# pc-001.net
KiCad netlist of a schematic drawn in EAGLE
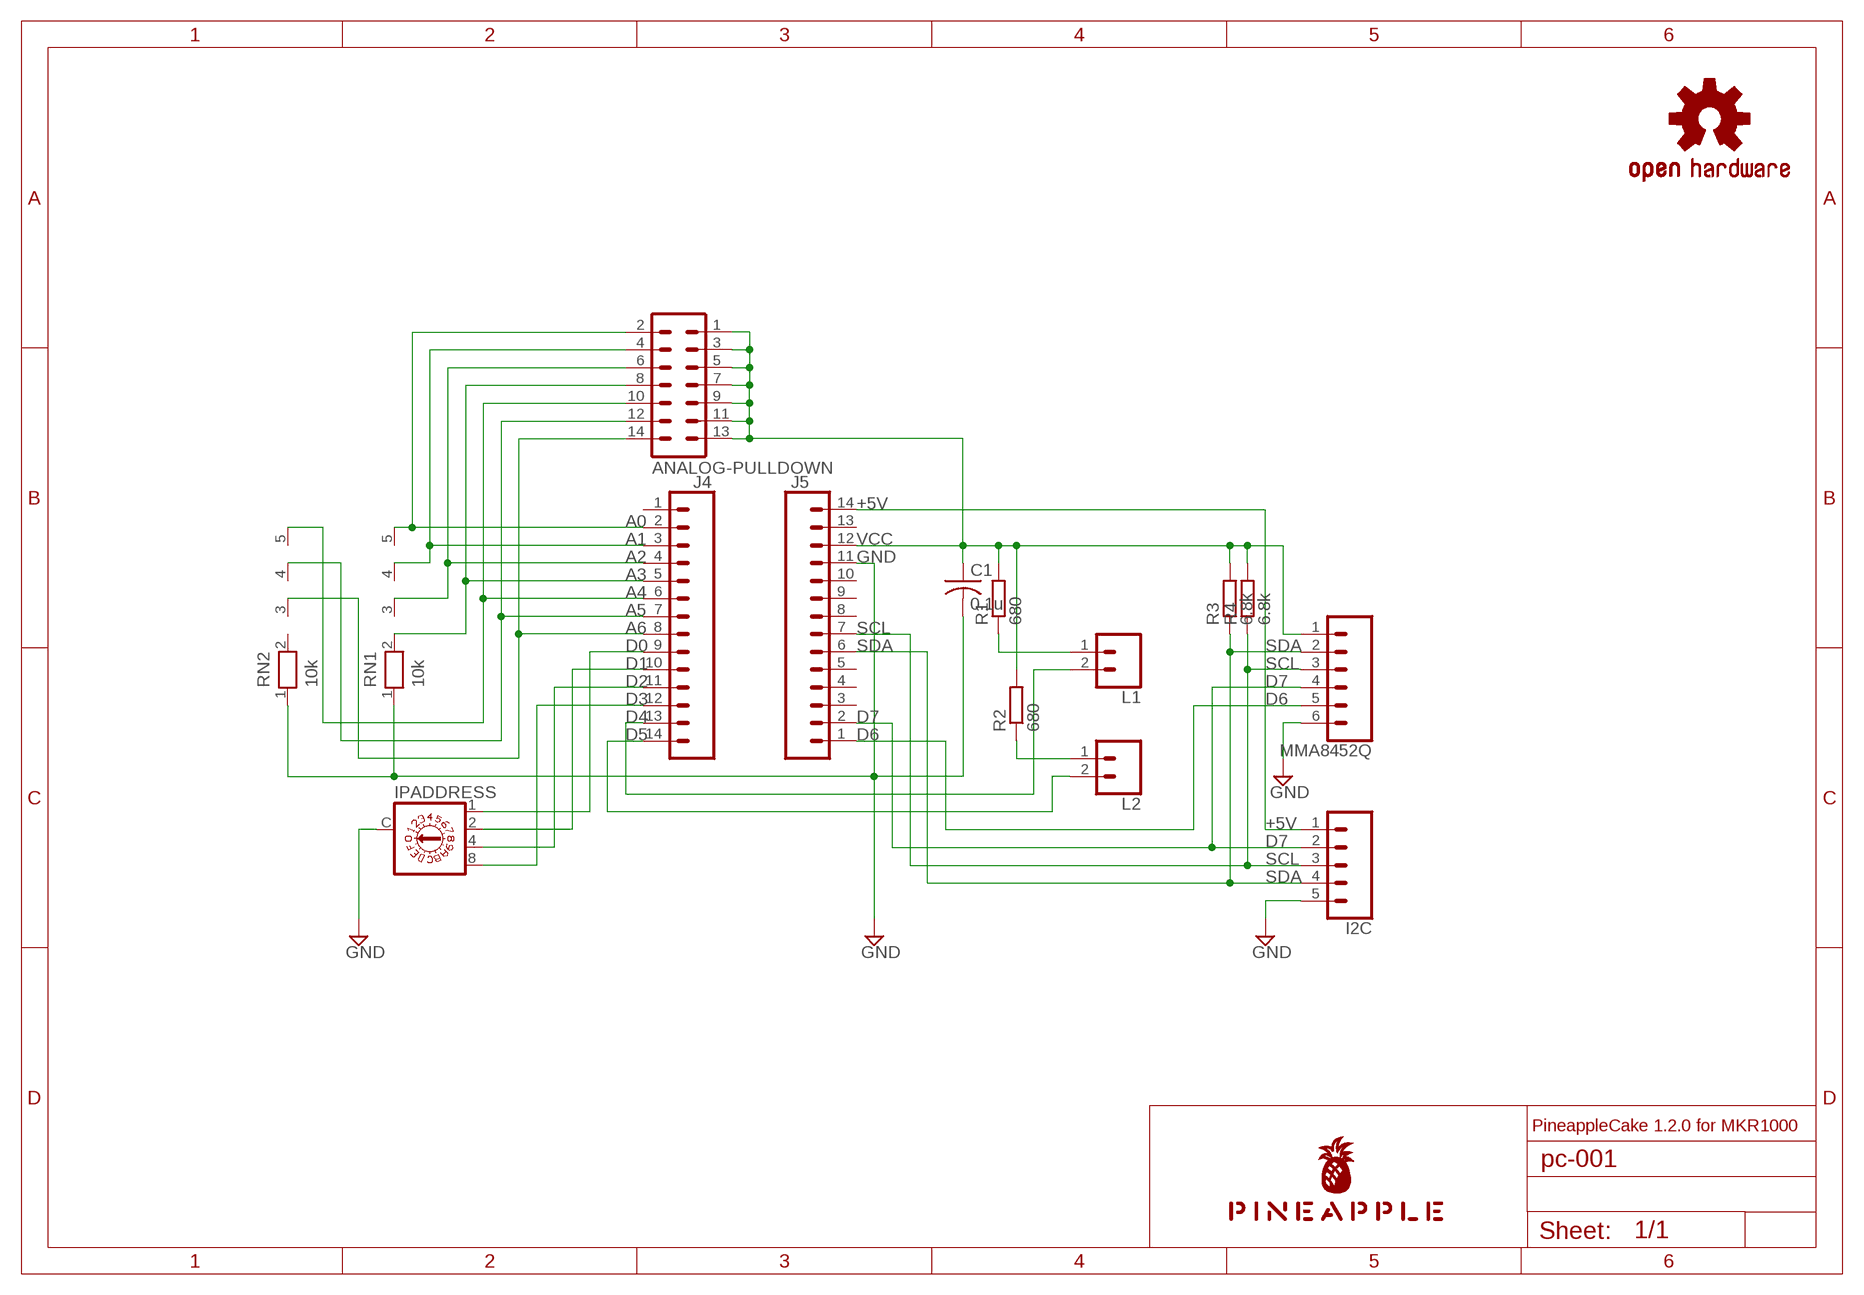
[diagram p0: schematic, sheet 1]

(export (version "E")
  (design (tool "Eeschema 10.0.6"))
  (components
    (comp (ref "ANALOG-PULLDOWN")
      (value "ML14L")
      (footprint "eagle-import:ML14L")
      (libsource (lib "eagle-import") (part "ML14L"))
    )
    (comp (ref "C1")
      (value "0.1u")
      (footprint "eagle-import:C025-025X050")
      (libsource (lib "eagle-import") (part "C-US025-025X050"))
    )
    (comp (ref "I2C")
      (value "CONN_05SMD")
      (footprint "eagle-import:1X05_1MM")
      (libsource (lib "eagle-import") (part "CONN_05SMD"))
    )
    (comp (ref "IPADDRESS")
      (value "A1353HEX")
      (footprint "eagle-import:A1353HEX")
      (libsource (lib "eagle-import") (part "A1353HEX"))
    )
    (comp (ref "J4")
      (value "DNP")
      (footprint "eagle-import:1X14")
      (libsource (lib "eagle-import") (part "CONN_14"))
    )
    (comp (ref "J5")
      (value "DNP")
      (footprint "eagle-import:1X14")
      (libsource (lib "eagle-import") (part "CONN_14"))
    )
    (comp (ref "L1")
      (value "CONN_02-JST-2-PTH-NO_SILK")
      (footprint "eagle-import:JST-2-PTH-NS")
      (libsource (lib "eagle-import") (part "CONN_02-JST-2-PTH-NO_SILK"))
    )
    (comp (ref "L2")
      (value "CONN_02-JST-2-PTH-NO_SILK")
      (footprint "eagle-import:JST-2-PTH-NS")
      (libsource (lib "eagle-import") (part "CONN_02-JST-2-PTH-NO_SILK"))
    )
    (comp (ref "LOGO1")
      (value "OSHW-LOGOS-COPPER")
      (footprint "eagle-import:OSHW-LOGO-S_COPPER")
      (libsource (lib "eagle-import") (part "OSHW-LOGOS-COPPER"))
    )
    (comp (ref "MMA8452Q")
      (value "CONN_06NO_SILK_FEMALE_PTH")
      (footprint "eagle-import:1X06_NO_SILK")
      (libsource (lib "eagle-import") (part "CONN_06NO_SILK_FEMALE_PTH"))
    )
    (comp (ref "R1")
      (value "680")
      (footprint "eagle-import:0204_5")
      (libsource (lib "eagle-import") (part "R-EU_0204/5"))
    )
    (comp (ref "R2")
      (value "680")
      (footprint "eagle-import:0204_5")
      (libsource (lib "eagle-import") (part "R-EU_0204/5"))
    )
    (comp (ref "R3")
      (value "6.8k")
      (footprint "eagle-import:0204_5")
      (libsource (lib "eagle-import") (part "R-EU_0204/5"))
    )
    (comp (ref "R4")
      (value "6.8k")
      (footprint "eagle-import:0204_5")
      (libsource (lib "eagle-import") (part "R-EU_0204/5"))
    )
    (comp (ref "RN1")
      (value "10k")
      (footprint "eagle-import:RN-5")
      (libsource (lib "eagle-import") (part "RN04"))
    )
    (comp (ref "RN2")
      (value "10k")
      (footprint "eagle-import:RN-5")
      (libsource (lib "eagle-import") (part "RN04"))
    )
    (comp (ref "U$1")
      (value "PINEAPPLE450")
      (footprint "eagle-import:PINEAPPLE450")
      (libsource (lib "eagle-import") (part "PINEAPPLE450"))
    )
  )
  (nets
    (net (code "1") (name "/+5V") (class "Default")
      (node (ref "I2C") (pin "1") (pinfunction "1_1") (pintype "passive"))
      (node (ref "J5") (pin "14") (pinfunction "14_14") (pintype "passive"))
    )
    (net (code "2") (name "/A0") (class "Default")
      (node (ref "ANALOG-PULLDOWN") (pin "2") (pinfunction "2_2") (pintype "passive"))
      (node (ref "J4") (pin "2") (pinfunction "2_2") (pintype "passive"))
      (node (ref "RN1") (pin "5") (pinfunction "5_5") (pintype "passive"))
    )
    (net (code "3") (name "/A1") (class "Default")
      (node (ref "ANALOG-PULLDOWN") (pin "4") (pinfunction "4_4") (pintype "passive"))
      (node (ref "J4") (pin "3") (pinfunction "3_3") (pintype "passive"))
      (node (ref "RN1") (pin "4") (pinfunction "4_4") (pintype "passive"))
    )
    (net (code "4") (name "/A2") (class "Default")
      (node (ref "ANALOG-PULLDOWN") (pin "6") (pinfunction "6_6") (pintype "passive"))
      (node (ref "J4") (pin "4") (pinfunction "4_4") (pintype "passive"))
      (node (ref "RN1") (pin "3") (pinfunction "3_3") (pintype "passive"))
    )
    (net (code "5") (name "/A3") (class "Default")
      (node (ref "ANALOG-PULLDOWN") (pin "8") (pinfunction "8_8") (pintype "passive"))
      (node (ref "J4") (pin "5") (pinfunction "5_5") (pintype "passive"))
      (node (ref "RN1") (pin "2") (pinfunction "2_2") (pintype "passive"))
    )
    (net (code "6") (name "/A4") (class "Default")
      (node (ref "ANALOG-PULLDOWN") (pin "10") (pinfunction "10_10") (pintype "passive"))
      (node (ref "J4") (pin "6") (pinfunction "6_6") (pintype "passive"))
      (node (ref "RN2") (pin "5") (pinfunction "5_5") (pintype "passive"))
    )
    (net (code "7") (name "/A5") (class "Default")
      (node (ref "ANALOG-PULLDOWN") (pin "12") (pinfunction "12_12") (pintype "passive"))
      (node (ref "J4") (pin "7") (pinfunction "7_7") (pintype "passive"))
      (node (ref "RN2") (pin "4") (pinfunction "4_4") (pintype "passive"))
    )
    (net (code "8") (name "/A6") (class "Default")
      (node (ref "ANALOG-PULLDOWN") (pin "14") (pinfunction "14_14") (pintype "passive"))
      (node (ref "J4") (pin "8") (pinfunction "8_8") (pintype "passive"))
      (node (ref "RN2") (pin "3") (pinfunction "3_3") (pintype "passive"))
    )
    (net (code "9") (name "/D0") (class "Default")
      (node (ref "IPADDRESS") (pin "1") (pinfunction "1_1") (pintype "passive"))
      (node (ref "J4") (pin "9") (pinfunction "9_9") (pintype "passive"))
    )
    (net (code "10") (name "/D1") (class "Default")
      (node (ref "IPADDRESS") (pin "2") (pinfunction "2_2") (pintype "passive"))
      (node (ref "J4") (pin "10") (pinfunction "10_10") (pintype "passive"))
    )
    (net (code "11") (name "/D2") (class "Default")
      (node (ref "IPADDRESS") (pin "4") (pinfunction "4_4") (pintype "passive"))
      (node (ref "J4") (pin "11") (pinfunction "11_11") (pintype "passive"))
    )
    (net (code "12") (name "/D3") (class "Default")
      (node (ref "IPADDRESS") (pin "8") (pinfunction "8_8") (pintype "passive"))
      (node (ref "J4") (pin "12") (pinfunction "12_12") (pintype "passive"))
    )
    (net (code "13") (name "/D4") (class "Default")
      (node (ref "J4") (pin "13") (pinfunction "13_13") (pintype "passive"))
      (node (ref "L1") (pin "2") (pinfunction "2_2") (pintype "passive"))
    )
    (net (code "14") (name "/D5") (class "Default")
      (node (ref "J4") (pin "14") (pinfunction "14_14") (pintype "passive"))
      (node (ref "L2") (pin "2") (pinfunction "2_2") (pintype "passive"))
    )
    (net (code "15") (name "/D6") (class "Default")
      (node (ref "J5") (pin "1") (pinfunction "1_1") (pintype "passive"))
      (node (ref "MMA8452Q") (pin "5") (pinfunction "5_5") (pintype "passive"))
    )
    (net (code "16") (name "/D7") (class "Default")
      (node (ref "I2C") (pin "2") (pinfunction "2_2") (pintype "passive"))
      (node (ref "J5") (pin "2") (pinfunction "2_2") (pintype "passive"))
      (node (ref "MMA8452Q") (pin "4") (pinfunction "4_4") (pintype "passive"))
    )
    (net (code "17") (name "/SCL") (class "Default")
      (node (ref "I2C") (pin "3") (pinfunction "3_3") (pintype "passive"))
      (node (ref "J5") (pin "7") (pinfunction "7_7") (pintype "passive"))
      (node (ref "MMA8452Q") (pin "3") (pinfunction "3_3") (pintype "passive"))
      (node (ref "R4") (pin "1") (pinfunction "1_1") (pintype "passive"))
    )
    (net (code "18") (name "/SDA") (class "Default")
      (node (ref "I2C") (pin "4") (pinfunction "4_4") (pintype "passive"))
      (node (ref "J5") (pin "6") (pinfunction "6_6") (pintype "passive"))
      (node (ref "MMA8452Q") (pin "2") (pinfunction "2_2") (pintype "passive"))
      (node (ref "R3") (pin "1") (pinfunction "1_1") (pintype "passive"))
    )
    (net (code "19") (name "/VCC") (class "Default")
      (node (ref "ANALOG-PULLDOWN") (pin "1") (pinfunction "1_1") (pintype "passive"))
      (node (ref "ANALOG-PULLDOWN") (pin "11") (pinfunction "11_11") (pintype "passive"))
      (node (ref "ANALOG-PULLDOWN") (pin "13") (pinfunction "13_13") (pintype "passive"))
      (node (ref "ANALOG-PULLDOWN") (pin "3") (pinfunction "3_3") (pintype "passive"))
      (node (ref "ANALOG-PULLDOWN") (pin "5") (pinfunction "5_5") (pintype "passive"))
      (node (ref "ANALOG-PULLDOWN") (pin "7") (pinfunction "7_7") (pintype "passive"))
      (node (ref "ANALOG-PULLDOWN") (pin "9") (pinfunction "9_9") (pintype "passive"))
      (node (ref "C1") (pin "1") (pinfunction "1_1") (pintype "passive"))
      (node (ref "J5") (pin "12") (pinfunction "12_12") (pintype "passive"))
      (node (ref "MMA8452Q") (pin "1") (pinfunction "1_1") (pintype "passive"))
      (node (ref "R1") (pin "2") (pinfunction "2_2") (pintype "passive"))
      (node (ref "R2") (pin "2") (pinfunction "2_2") (pintype "passive"))
      (node (ref "R3") (pin "2") (pinfunction "2_2") (pintype "passive"))
      (node (ref "R4") (pin "2") (pinfunction "2_2") (pintype "passive"))
    )
    (net (code "20") (name "GND") (class "Default")
      (node (ref "C1") (pin "2") (pinfunction "2_2") (pintype "passive"))
      (node (ref "I2C") (pin "5") (pinfunction "5_5") (pintype "passive"))
      (node (ref "IPADDRESS") (pin "C") (pinfunction "C_C") (pintype "passive"))
      (node (ref "J5") (pin "11") (pinfunction "11_11") (pintype "passive"))
      (node (ref "MMA8452Q") (pin "6") (pinfunction "6_6") (pintype "passive"))
      (node (ref "RN1") (pin "1") (pinfunction "1_1") (pintype "passive"))
      (node (ref "RN2") (pin "1") (pinfunction "1_1") (pintype "passive"))
    )
    (net (code "21") (name "Net-(L1-Pad1)") (class "Default")
      (node (ref "L1") (pin "1") (pinfunction "1_1") (pintype "passive"))
      (node (ref "R1") (pin "1") (pinfunction "1_1") (pintype "passive"))
    )
    (net (code "22") (name "Net-(L2-Pad1)") (class "Default")
      (node (ref "L2") (pin "1") (pinfunction "1_1") (pintype "passive"))
      (node (ref "R2") (pin "1") (pinfunction "1_1") (pintype "passive"))
    )
    (net (code "23") (name "unconnected-(J4-Pad1)") (class "Default")
      (node (ref "J4") (pin "1") (pinfunction "1_1") (pintype "passive"))
    )
    (net (code "24") (name "unconnected-(J5-Pad3)") (class "Default")
      (node (ref "J5") (pin "3") (pinfunction "3_3") (pintype "passive"))
    )
    (net (code "25") (name "unconnected-(J5-Pad4)") (class "Default")
      (node (ref "J5") (pin "4") (pinfunction "4_4") (pintype "passive"))
    )
    (net (code "26") (name "unconnected-(J5-Pad5)") (class "Default")
      (node (ref "J5") (pin "5") (pinfunction "5_5") (pintype "passive"))
    )
    (net (code "27") (name "unconnected-(J5-Pad8)") (class "Default")
      (node (ref "J5") (pin "8") (pinfunction "8_8") (pintype "passive"))
    )
    (net (code "28") (name "unconnected-(J5-Pad9)") (class "Default")
      (node (ref "J5") (pin "9") (pinfunction "9_9") (pintype "passive"))
    )
    (net (code "29") (name "unconnected-(J5-Pad10)") (class "Default")
      (node (ref "J5") (pin "10") (pinfunction "10_10") (pintype "passive"))
    )
    (net (code "30") (name "unconnected-(J5-Pad13)") (class "Default")
      (node (ref "J5") (pin "13") (pinfunction "13_13") (pintype "passive"))
    )
    (net (code "31") (name "unconnected-(RN2-Pad2)") (class "Default")
      (node (ref "RN2") (pin "2") (pinfunction "2_2") (pintype "passive"))
    )
  )
)
